# Sheet2.net
KiCad netlist of a schematic drawn in Altium Designer
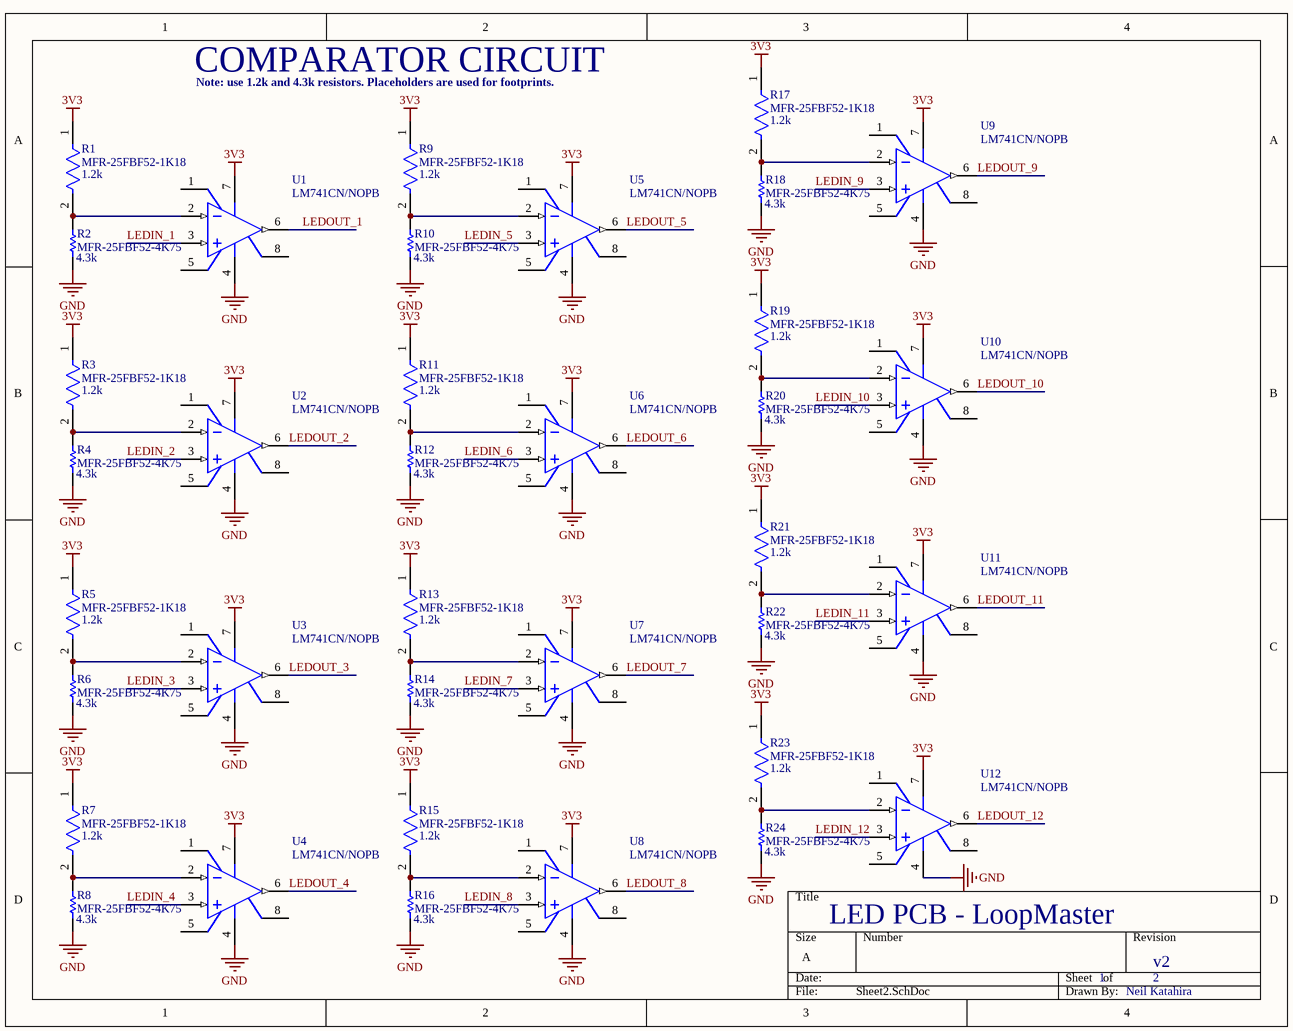
[diagram p0: Sheet2.SchDoc]

(export (version "E")
  (design (tool "Eeschema 10.0.6"))
  (components
    (comp (ref "R1")
      (value "MFR-25FBF52-1K18")
      (footprint "FP-MFR-25-MFG")
      (description "1.18 kOhms ±1% 0.25W, 1/4W Through Hole Resistor Axial  Metal Film")
      (fields (field (name "MANUFACTURER") "Yageo"))
      (libsource (lib "Altium Content Vault") (part "1029c3af85768c4190bb7ad29bc67b5"))
    )
    (comp (ref "R2")
      (value "MFR-25FBF52-4K75")
      (footprint "RESA60-630X240")
      (description "Axial Resistor, 4.75 KOhm, +/- 1%, 0.25 W, -55 to 155 degC, 2-Pin THD, RoHS, Bulk")
      (fields (field (name "TOLERANCE") "10%"))
      (libsource (lib "Altium Content Vault") (part "RES-2"))
    )
    (comp (ref "R3")
      (value "MFR-25FBF52-1K18")
      (footprint "FP-MFR-25-MFG")
      (description "1.18 kOhms ±1% 0.25W, 1/4W Through Hole Resistor Axial  Metal Film")
      (fields (field (name "MANUFACTURER") "Yageo"))
      (libsource (lib "Altium Content Vault") (part "1029c3af85768c4190bb7ad29bc67b5"))
    )
    (comp (ref "R4")
      (value "MFR-25FBF52-4K75")
      (footprint "RESA60-630X240")
      (description "Axial Resistor, 4.75 KOhm, +/- 1%, 0.25 W, -55 to 155 degC, 2-Pin THD, RoHS, Bulk")
      (fields (field (name "TOLERANCE") "10%"))
      (libsource (lib "Altium Content Vault") (part "RES-2"))
    )
    (comp (ref "R5")
      (value "MFR-25FBF52-1K18")
      (footprint "FP-MFR-25-MFG")
      (description "1.18 kOhms ±1% 0.25W, 1/4W Through Hole Resistor Axial  Metal Film")
      (fields (field (name "MANUFACTURER") "Yageo"))
      (libsource (lib "Altium Content Vault") (part "1029c3af85768c4190bb7ad29bc67b5"))
    )
    (comp (ref "R6")
      (value "MFR-25FBF52-4K75")
      (footprint "RESA60-630X240")
      (description "Axial Resistor, 4.75 KOhm, +/- 1%, 0.25 W, -55 to 155 degC, 2-Pin THD, RoHS, Bulk")
      (fields (field (name "TOLERANCE") "10%"))
      (libsource (lib "Altium Content Vault") (part "RES-2"))
    )
    (comp (ref "R7")
      (value "MFR-25FBF52-1K18")
      (footprint "FP-MFR-25-MFG")
      (description "1.18 kOhms ±1% 0.25W, 1/4W Through Hole Resistor Axial  Metal Film")
      (fields (field (name "MANUFACTURER") "Yageo"))
      (libsource (lib "Altium Content Vault") (part "1029c3af85768c4190bb7ad29bc67b5"))
    )
    (comp (ref "R8")
      (value "MFR-25FBF52-4K75")
      (footprint "RESA60-630X240")
      (description "Axial Resistor, 4.75 KOhm, +/- 1%, 0.25 W, -55 to 155 degC, 2-Pin THD, RoHS, Bulk")
      (fields (field (name "TOLERANCE") "10%"))
      (libsource (lib "Altium Content Vault") (part "RES-2"))
    )
    (comp (ref "R9")
      (value "MFR-25FBF52-1K18")
      (footprint "FP-MFR-25-MFG")
      (description "1.18 kOhms ±1% 0.25W, 1/4W Through Hole Resistor Axial  Metal Film")
      (fields (field (name "MANUFACTURER") "Yageo"))
      (libsource (lib "Altium Content Vault") (part "1029c3af85768c4190bb7ad29bc67b5"))
    )
    (comp (ref "R10")
      (value "MFR-25FBF52-4K75")
      (footprint "RESA60-630X240")
      (description "Axial Resistor, 4.75 KOhm, +/- 1%, 0.25 W, -55 to 155 degC, 2-Pin THD, RoHS, Bulk")
      (fields (field (name "TOLERANCE") "10%"))
      (libsource (lib "Altium Content Vault") (part "RES-2"))
    )
    (comp (ref "R11")
      (value "MFR-25FBF52-1K18")
      (footprint "FP-MFR-25-MFG")
      (description "1.18 kOhms ±1% 0.25W, 1/4W Through Hole Resistor Axial  Metal Film")
      (fields (field (name "MANUFACTURER") "Yageo"))
      (libsource (lib "Altium Content Vault") (part "1029c3af85768c4190bb7ad29bc67b5"))
    )
    (comp (ref "R12")
      (value "MFR-25FBF52-4K75")
      (footprint "RESA60-630X240")
      (description "Axial Resistor, 4.75 KOhm, +/- 1%, 0.25 W, -55 to 155 degC, 2-Pin THD, RoHS, Bulk")
      (fields (field (name "TOLERANCE") "10%"))
      (libsource (lib "Altium Content Vault") (part "RES-2"))
    )
    (comp (ref "R13")
      (value "MFR-25FBF52-1K18")
      (footprint "FP-MFR-25-MFG")
      (description "1.18 kOhms ±1% 0.25W, 1/4W Through Hole Resistor Axial  Metal Film")
      (fields (field (name "MANUFACTURER") "Yageo"))
      (libsource (lib "Altium Content Vault") (part "1029c3af85768c4190bb7ad29bc67b5"))
    )
    (comp (ref "R14")
      (value "MFR-25FBF52-4K75")
      (footprint "RESA60-630X240")
      (description "Axial Resistor, 4.75 KOhm, +/- 1%, 0.25 W, -55 to 155 degC, 2-Pin THD, RoHS, Bulk")
      (fields (field (name "TOLERANCE") "10%"))
      (libsource (lib "Altium Content Vault") (part "RES-2"))
    )
    (comp (ref "R15")
      (value "MFR-25FBF52-1K18")
      (footprint "FP-MFR-25-MFG")
      (description "1.18 kOhms ±1% 0.25W, 1/4W Through Hole Resistor Axial  Metal Film")
      (fields (field (name "MANUFACTURER") "Yageo"))
      (libsource (lib "Altium Content Vault") (part "1029c3af85768c4190bb7ad29bc67b5"))
    )
    (comp (ref "R16")
      (value "MFR-25FBF52-4K75")
      (footprint "RESA60-630X240")
      (description "Axial Resistor, 4.75 KOhm, +/- 1%, 0.25 W, -55 to 155 degC, 2-Pin THD, RoHS, Bulk")
      (fields (field (name "TOLERANCE") "10%"))
      (libsource (lib "Altium Content Vault") (part "RES-2"))
    )
    (comp (ref "R17")
      (value "MFR-25FBF52-1K18")
      (footprint "FP-MFR-25-MFG")
      (description "1.18 kOhms ±1% 0.25W, 1/4W Through Hole Resistor Axial  Metal Film")
      (fields (field (name "MANUFACTURER") "Yageo"))
      (libsource (lib "Altium Content Vault") (part "1029c3af85768c4190bb7ad29bc67b5"))
    )
    (comp (ref "R18")
      (value "MFR-25FBF52-4K75")
      (footprint "RESA60-630X240")
      (description "Axial Resistor, 4.75 KOhm, +/- 1%, 0.25 W, -55 to 155 degC, 2-Pin THD, RoHS, Bulk")
      (fields (field (name "TOLERANCE") "10%"))
      (libsource (lib "Altium Content Vault") (part "RES-2"))
    )
    (comp (ref "R19")
      (value "MFR-25FBF52-1K18")
      (footprint "FP-MFR-25-MFG")
      (description "1.18 kOhms ±1% 0.25W, 1/4W Through Hole Resistor Axial  Metal Film")
      (fields (field (name "MANUFACTURER") "Yageo"))
      (libsource (lib "Altium Content Vault") (part "1029c3af85768c4190bb7ad29bc67b5"))
    )
    (comp (ref "R20")
      (value "MFR-25FBF52-4K75")
      (footprint "RESA60-630X240")
      (description "Axial Resistor, 4.75 KOhm, +/- 1%, 0.25 W, -55 to 155 degC, 2-Pin THD, RoHS, Bulk")
      (fields (field (name "TOLERANCE") "10%"))
      (libsource (lib "Altium Content Vault") (part "RES-2"))
    )
    (comp (ref "R21")
      (value "MFR-25FBF52-1K18")
      (footprint "FP-MFR-25-MFG")
      (description "1.18 kOhms ±1% 0.25W, 1/4W Through Hole Resistor Axial  Metal Film")
      (fields (field (name "MANUFACTURER") "Yageo"))
      (libsource (lib "Altium Content Vault") (part "1029c3af85768c4190bb7ad29bc67b5"))
    )
    (comp (ref "R22")
      (value "MFR-25FBF52-4K75")
      (footprint "RESA60-630X240")
      (description "Axial Resistor, 4.75 KOhm, +/- 1%, 0.25 W, -55 to 155 degC, 2-Pin THD, RoHS, Bulk")
      (fields (field (name "TOLERANCE") "10%"))
      (libsource (lib "Altium Content Vault") (part "RES-2"))
    )
    (comp (ref "R23")
      (value "MFR-25FBF52-1K18")
      (footprint "FP-MFR-25-MFG")
      (description "1.18 kOhms ±1% 0.25W, 1/4W Through Hole Resistor Axial  Metal Film")
      (fields (field (name "MANUFACTURER") "Yageo"))
      (libsource (lib "Altium Content Vault") (part "1029c3af85768c4190bb7ad29bc67b5"))
    )
    (comp (ref "R24")
      (value "MFR-25FBF52-4K75")
      (footprint "RESA60-630X240")
      (description "Axial Resistor, 4.75 KOhm, +/- 1%, 0.25 W, -55 to 155 degC, 2-Pin THD, RoHS, Bulk")
      (fields (field (name "TOLERANCE") "10%"))
      (libsource (lib "Altium Content Vault") (part "RES-2"))
    )
    (comp (ref "U1")
      (value "LM741CN/NOPB")
      (footprint "P0008A")
      (description "Operational Amplifier, 8-pin MDIP, Pb-Free")
      (fields (field (name "MANUFACTURER") "Texas Instruments"))
      (libsource (lib "Altium Content Vault") (part "AMP-OPA-LM741-8"))
    )
    (comp (ref "U2")
      (value "LM741CN/NOPB")
      (footprint "P0008A")
      (description "Operational Amplifier, 8-pin MDIP, Pb-Free")
      (fields (field (name "MANUFACTURER") "Texas Instruments"))
      (libsource (lib "Altium Content Vault") (part "AMP-OPA-LM741-8"))
    )
    (comp (ref "U3")
      (value "LM741CN/NOPB")
      (footprint "P0008A")
      (description "Operational Amplifier, 8-pin MDIP, Pb-Free")
      (fields (field (name "MANUFACTURER") "Texas Instruments"))
      (libsource (lib "Altium Content Vault") (part "AMP-OPA-LM741-8"))
    )
    (comp (ref "U4")
      (value "LM741CN/NOPB")
      (footprint "P0008A")
      (description "Operational Amplifier, 8-pin MDIP, Pb-Free")
      (fields (field (name "MANUFACTURER") "Texas Instruments"))
      (libsource (lib "Altium Content Vault") (part "AMP-OPA-LM741-8"))
    )
    (comp (ref "U5")
      (value "LM741CN/NOPB")
      (footprint "P0008A")
      (description "Operational Amplifier, 8-pin MDIP, Pb-Free")
      (fields (field (name "MANUFACTURER") "Texas Instruments"))
      (libsource (lib "Altium Content Vault") (part "AMP-OPA-LM741-8"))
    )
    (comp (ref "U6")
      (value "LM741CN/NOPB")
      (footprint "P0008A")
      (description "Operational Amplifier, 8-pin MDIP, Pb-Free")
      (fields (field (name "MANUFACTURER") "Texas Instruments"))
      (libsource (lib "Altium Content Vault") (part "AMP-OPA-LM741-8"))
    )
    (comp (ref "U7")
      (value "LM741CN/NOPB")
      (footprint "P0008A")
      (description "Operational Amplifier, 8-pin MDIP, Pb-Free")
      (fields (field (name "MANUFACTURER") "Texas Instruments"))
      (libsource (lib "Altium Content Vault") (part "AMP-OPA-LM741-8"))
    )
    (comp (ref "U8")
      (value "LM741CN/NOPB")
      (footprint "P0008A")
      (description "Operational Amplifier, 8-pin MDIP, Pb-Free")
      (fields (field (name "MANUFACTURER") "Texas Instruments"))
      (libsource (lib "Altium Content Vault") (part "AMP-OPA-LM741-8"))
    )
    (comp (ref "U9")
      (value "LM741CN/NOPB")
      (footprint "P0008A")
      (description "Operational Amplifier, 8-pin MDIP, Pb-Free")
      (fields (field (name "MANUFACTURER") "Texas Instruments"))
      (libsource (lib "Altium Content Vault") (part "AMP-OPA-LM741-8"))
    )
    (comp (ref "U10")
      (value "LM741CN/NOPB")
      (footprint "P0008A")
      (description "Operational Amplifier, 8-pin MDIP, Pb-Free")
      (fields (field (name "MANUFACTURER") "Texas Instruments"))
      (libsource (lib "Altium Content Vault") (part "AMP-OPA-LM741-8"))
    )
    (comp (ref "U11")
      (value "LM741CN/NOPB")
      (footprint "P0008A")
      (description "Operational Amplifier, 8-pin MDIP, Pb-Free")
      (fields (field (name "MANUFACTURER") "Texas Instruments"))
      (libsource (lib "Altium Content Vault") (part "AMP-OPA-LM741-8"))
    )
    (comp (ref "U12")
      (value "LM741CN/NOPB")
      (footprint "P0008A")
      (description "Operational Amplifier, 8-pin MDIP, Pb-Free")
      (fields (field (name "MANUFACTURER") "Texas Instruments"))
      (libsource (lib "Altium Content Vault") (part "AMP-OPA-LM741-8"))
    )
  )
  (nets
    (net (code "1") (name "/LEDIN_1") (class "Default")
      (node (ref "U1") (pin "3") (pinfunction "IN+_3") (pintype "input"))
    )
    (net (code "2") (name "/LEDIN_2") (class "Default")
      (node (ref "U2") (pin "3") (pinfunction "IN+_3") (pintype "input"))
    )
    (net (code "3") (name "/LEDIN_3") (class "Default")
      (node (ref "U3") (pin "3") (pinfunction "IN+_3") (pintype "input"))
    )
    (net (code "4") (name "/LEDIN_4") (class "Default")
      (node (ref "U4") (pin "3") (pinfunction "IN+_3") (pintype "input"))
    )
    (net (code "5") (name "/LEDIN_5") (class "Default")
      (node (ref "U5") (pin "3") (pinfunction "IN+_3") (pintype "input"))
    )
    (net (code "6") (name "/LEDIN_6") (class "Default")
      (node (ref "U6") (pin "3") (pinfunction "IN+_3") (pintype "input"))
    )
    (net (code "7") (name "/LEDIN_7") (class "Default")
      (node (ref "U7") (pin "3") (pinfunction "IN+_3") (pintype "input"))
    )
    (net (code "8") (name "/LEDIN_8") (class "Default")
      (node (ref "U8") (pin "3") (pinfunction "IN+_3") (pintype "input"))
    )
    (net (code "9") (name "/LEDIN_9") (class "Default")
      (node (ref "U9") (pin "3") (pinfunction "IN+_3") (pintype "input"))
    )
    (net (code "10") (name "/LEDIN_10") (class "Default")
      (node (ref "U10") (pin "3") (pinfunction "IN+_3") (pintype "input"))
    )
    (net (code "11") (name "/LEDIN_11") (class "Default")
      (node (ref "U11") (pin "3") (pinfunction "IN+_3") (pintype "input"))
    )
    (net (code "12") (name "/LEDIN_12") (class "Default")
      (node (ref "U12") (pin "3") (pinfunction "IN+_3") (pintype "input"))
    )
    (net (code "13") (name "/LEDOUT_1") (class "Default")
      (node (ref "U1") (pin "6") (pinfunction "OUT_6") (pintype "output"))
    )
    (net (code "14") (name "/LEDOUT_2") (class "Default")
      (node (ref "U2") (pin "6") (pinfunction "OUT_6") (pintype "output"))
    )
    (net (code "15") (name "/LEDOUT_3") (class "Default")
      (node (ref "U3") (pin "6") (pinfunction "OUT_6") (pintype "output"))
    )
    (net (code "16") (name "/LEDOUT_4") (class "Default")
      (node (ref "U4") (pin "6") (pinfunction "OUT_6") (pintype "output"))
    )
    (net (code "17") (name "/LEDOUT_5") (class "Default")
      (node (ref "U5") (pin "6") (pinfunction "OUT_6") (pintype "output"))
    )
    (net (code "18") (name "/LEDOUT_6") (class "Default")
      (node (ref "U6") (pin "6") (pinfunction "OUT_6") (pintype "output"))
    )
    (net (code "19") (name "/LEDOUT_7") (class "Default")
      (node (ref "U7") (pin "6") (pinfunction "OUT_6") (pintype "output"))
    )
    (net (code "20") (name "/LEDOUT_8") (class "Default")
      (node (ref "U8") (pin "6") (pinfunction "OUT_6") (pintype "output"))
    )
    (net (code "21") (name "/LEDOUT_9") (class "Default")
      (node (ref "U9") (pin "6") (pinfunction "OUT_6") (pintype "output"))
    )
    (net (code "22") (name "/LEDOUT_10") (class "Default")
      (node (ref "U10") (pin "6") (pinfunction "OUT_6") (pintype "output"))
    )
    (net (code "23") (name "/LEDOUT_11") (class "Default")
      (node (ref "U11") (pin "6") (pinfunction "OUT_6") (pintype "output"))
    )
    (net (code "24") (name "/LEDOUT_12") (class "Default")
      (node (ref "U12") (pin "6") (pinfunction "OUT_6") (pintype "output"))
    )
    (net (code "25") (name "3V3") (class "Default")
      (node (ref "R1") (pin "1") (pinfunction "1_1") (pintype "passive"))
      (node (ref "R11") (pin "1") (pinfunction "1_1") (pintype "passive"))
      (node (ref "R13") (pin "1") (pinfunction "1_1") (pintype "passive"))
      (node (ref "R15") (pin "1") (pinfunction "1_1") (pintype "passive"))
      (node (ref "R17") (pin "1") (pinfunction "1_1") (pintype "passive"))
      (node (ref "R19") (pin "1") (pinfunction "1_1") (pintype "passive"))
      (node (ref "R21") (pin "1") (pinfunction "1_1") (pintype "passive"))
      (node (ref "R23") (pin "1") (pinfunction "1_1") (pintype "passive"))
      (node (ref "R3") (pin "1") (pinfunction "1_1") (pintype "passive"))
      (node (ref "R5") (pin "1") (pinfunction "1_1") (pintype "passive"))
      (node (ref "R7") (pin "1") (pinfunction "1_1") (pintype "passive"))
      (node (ref "R9") (pin "1") (pinfunction "1_1") (pintype "passive"))
      (node (ref "U1") (pin "7") (pinfunction "V+_7") (pintype "power_in"))
      (node (ref "U10") (pin "7") (pinfunction "V+_7") (pintype "power_in"))
      (node (ref "U11") (pin "7") (pinfunction "V+_7") (pintype "power_in"))
      (node (ref "U12") (pin "7") (pinfunction "V+_7") (pintype "power_in"))
      (node (ref "U2") (pin "7") (pinfunction "V+_7") (pintype "power_in"))
      (node (ref "U3") (pin "7") (pinfunction "V+_7") (pintype "power_in"))
      (node (ref "U4") (pin "7") (pinfunction "V+_7") (pintype "power_in"))
      (node (ref "U5") (pin "7") (pinfunction "V+_7") (pintype "power_in"))
      (node (ref "U6") (pin "7") (pinfunction "V+_7") (pintype "power_in"))
      (node (ref "U7") (pin "7") (pinfunction "V+_7") (pintype "power_in"))
      (node (ref "U8") (pin "7") (pinfunction "V+_7") (pintype "power_in"))
      (node (ref "U9") (pin "7") (pinfunction "V+_7") (pintype "power_in"))
    )
    (net (code "26") (name "GND") (class "Default")
      (node (ref "R10") (pin "1") (pinfunction "1_1") (pintype "passive"))
      (node (ref "R12") (pin "1") (pinfunction "1_1") (pintype "passive"))
      (node (ref "R14") (pin "1") (pinfunction "1_1") (pintype "passive"))
      (node (ref "R16") (pin "1") (pinfunction "1_1") (pintype "passive"))
      (node (ref "R18") (pin "1") (pinfunction "1_1") (pintype "passive"))
      (node (ref "R2") (pin "1") (pinfunction "1_1") (pintype "passive"))
      (node (ref "R20") (pin "1") (pinfunction "1_1") (pintype "passive"))
      (node (ref "R22") (pin "1") (pinfunction "1_1") (pintype "passive"))
      (node (ref "R24") (pin "1") (pinfunction "1_1") (pintype "passive"))
      (node (ref "R4") (pin "1") (pinfunction "1_1") (pintype "passive"))
      (node (ref "R6") (pin "1") (pinfunction "1_1") (pintype "passive"))
      (node (ref "R8") (pin "1") (pinfunction "1_1") (pintype "passive"))
      (node (ref "U1") (pin "4") (pinfunction "V-_4") (pintype "power_in"))
      (node (ref "U10") (pin "4") (pinfunction "V-_4") (pintype "power_in"))
      (node (ref "U11") (pin "4") (pinfunction "V-_4") (pintype "power_in"))
      (node (ref "U12") (pin "4") (pinfunction "V-_4") (pintype "power_in"))
      (node (ref "U2") (pin "4") (pinfunction "V-_4") (pintype "power_in"))
      (node (ref "U3") (pin "4") (pinfunction "V-_4") (pintype "power_in"))
      (node (ref "U4") (pin "4") (pinfunction "V-_4") (pintype "power_in"))
      (node (ref "U5") (pin "4") (pinfunction "V-_4") (pintype "power_in"))
      (node (ref "U6") (pin "4") (pinfunction "V-_4") (pintype "power_in"))
      (node (ref "U7") (pin "4") (pinfunction "V-_4") (pintype "power_in"))
      (node (ref "U8") (pin "4") (pinfunction "V-_4") (pintype "power_in"))
      (node (ref "U9") (pin "4") (pinfunction "V-_4") (pintype "power_in"))
    )
    (net (code "27") (name "Net-(U1-IN-)") (class "Default")
      (node (ref "R1") (pin "2") (pinfunction "2_2") (pintype "passive"))
      (node (ref "R2") (pin "2") (pinfunction "2_2") (pintype "passive"))
      (node (ref "U1") (pin "2") (pinfunction "IN-_2") (pintype "input"))
    )
    (net (code "28") (name "Net-(U2-IN-)") (class "Default")
      (node (ref "R3") (pin "2") (pinfunction "2_2") (pintype "passive"))
      (node (ref "R4") (pin "2") (pinfunction "2_2") (pintype "passive"))
      (node (ref "U2") (pin "2") (pinfunction "IN-_2") (pintype "input"))
    )
    (net (code "29") (name "Net-(U3-IN-)") (class "Default")
      (node (ref "R5") (pin "2") (pinfunction "2_2") (pintype "passive"))
      (node (ref "R6") (pin "2") (pinfunction "2_2") (pintype "passive"))
      (node (ref "U3") (pin "2") (pinfunction "IN-_2") (pintype "input"))
    )
    (net (code "30") (name "Net-(U4-IN-)") (class "Default")
      (node (ref "R7") (pin "2") (pinfunction "2_2") (pintype "passive"))
      (node (ref "R8") (pin "2") (pinfunction "2_2") (pintype "passive"))
      (node (ref "U4") (pin "2") (pinfunction "IN-_2") (pintype "input"))
    )
    (net (code "31") (name "Net-(U5-IN-)") (class "Default")
      (node (ref "R10") (pin "2") (pinfunction "2_2") (pintype "passive"))
      (node (ref "R9") (pin "2") (pinfunction "2_2") (pintype "passive"))
      (node (ref "U5") (pin "2") (pinfunction "IN-_2") (pintype "input"))
    )
    (net (code "32") (name "Net-(U6-IN-)") (class "Default")
      (node (ref "R11") (pin "2") (pinfunction "2_2") (pintype "passive"))
      (node (ref "R12") (pin "2") (pinfunction "2_2") (pintype "passive"))
      (node (ref "U6") (pin "2") (pinfunction "IN-_2") (pintype "input"))
    )
    (net (code "33") (name "Net-(U7-IN-)") (class "Default")
      (node (ref "R13") (pin "2") (pinfunction "2_2") (pintype "passive"))
      (node (ref "R14") (pin "2") (pinfunction "2_2") (pintype "passive"))
      (node (ref "U7") (pin "2") (pinfunction "IN-_2") (pintype "input"))
    )
    (net (code "34") (name "Net-(U8-IN-)") (class "Default")
      (node (ref "R15") (pin "2") (pinfunction "2_2") (pintype "passive"))
      (node (ref "R16") (pin "2") (pinfunction "2_2") (pintype "passive"))
      (node (ref "U8") (pin "2") (pinfunction "IN-_2") (pintype "input"))
    )
    (net (code "35") (name "Net-(U9-IN-)") (class "Default")
      (node (ref "R17") (pin "2") (pinfunction "2_2") (pintype "passive"))
      (node (ref "R18") (pin "2") (pinfunction "2_2") (pintype "passive"))
      (node (ref "U9") (pin "2") (pinfunction "IN-_2") (pintype "input"))
    )
    (net (code "36") (name "Net-(U10-IN-)") (class "Default")
      (node (ref "R19") (pin "2") (pinfunction "2_2") (pintype "passive"))
      (node (ref "R20") (pin "2") (pinfunction "2_2") (pintype "passive"))
      (node (ref "U10") (pin "2") (pinfunction "IN-_2") (pintype "input"))
    )
    (net (code "37") (name "Net-(U11-IN-)") (class "Default")
      (node (ref "R21") (pin "2") (pinfunction "2_2") (pintype "passive"))
      (node (ref "R22") (pin "2") (pinfunction "2_2") (pintype "passive"))
      (node (ref "U11") (pin "2") (pinfunction "IN-_2") (pintype "input"))
    )
    (net (code "38") (name "Net-(U12-IN-)") (class "Default")
      (node (ref "R23") (pin "2") (pinfunction "2_2") (pintype "passive"))
      (node (ref "R24") (pin "2") (pinfunction "2_2") (pintype "passive"))
      (node (ref "U12") (pin "2") (pinfunction "IN-_2") (pintype "input"))
    )
    (net (code "39") (name "unconnected-(U1-NC-Pad8)") (class "Default")
      (node (ref "U1") (pin "8") (pinfunction "NC_8") (pintype "passive"))
    )
    (net (code "40") (name "unconnected-(U1-OFS_NULL-Pad1)") (class "Default")
      (node (ref "U1") (pin "1") (pinfunction "OFS_NULL_1") (pintype "passive"))
    )
    (net (code "41") (name "unconnected-(U1-OFS_NULL-Pad5)") (class "Default")
      (node (ref "U1") (pin "5") (pinfunction "OFS_NULL_5") (pintype "passive"))
    )
    (net (code "42") (name "unconnected-(U2-NC-Pad8)") (class "Default")
      (node (ref "U2") (pin "8") (pinfunction "NC_8") (pintype "passive"))
    )
    (net (code "43") (name "unconnected-(U2-OFS_NULL-Pad1)") (class "Default")
      (node (ref "U2") (pin "1") (pinfunction "OFS_NULL_1") (pintype "passive"))
    )
    (net (code "44") (name "unconnected-(U2-OFS_NULL-Pad5)") (class "Default")
      (node (ref "U2") (pin "5") (pinfunction "OFS_NULL_5") (pintype "passive"))
    )
    (net (code "45") (name "unconnected-(U3-NC-Pad8)") (class "Default")
      (node (ref "U3") (pin "8") (pinfunction "NC_8") (pintype "passive"))
    )
    (net (code "46") (name "unconnected-(U3-OFS_NULL-Pad1)") (class "Default")
      (node (ref "U3") (pin "1") (pinfunction "OFS_NULL_1") (pintype "passive"))
    )
    (net (code "47") (name "unconnected-(U3-OFS_NULL-Pad5)") (class "Default")
      (node (ref "U3") (pin "5") (pinfunction "OFS_NULL_5") (pintype "passive"))
    )
    (net (code "48") (name "unconnected-(U4-NC-Pad8)") (class "Default")
      (node (ref "U4") (pin "8") (pinfunction "NC_8") (pintype "passive"))
    )
    (net (code "49") (name "unconnected-(U4-OFS_NULL-Pad1)") (class "Default")
      (node (ref "U4") (pin "1") (pinfunction "OFS_NULL_1") (pintype "passive"))
    )
    (net (code "50") (name "unconnected-(U4-OFS_NULL-Pad5)") (class "Default")
      (node (ref "U4") (pin "5") (pinfunction "OFS_NULL_5") (pintype "passive"))
    )
    (net (code "51") (name "unconnected-(U5-NC-Pad8)") (class "Default")
      (node (ref "U5") (pin "8") (pinfunction "NC_8") (pintype "passive"))
    )
    (net (code "52") (name "unconnected-(U5-OFS_NULL-Pad1)") (class "Default")
      (node (ref "U5") (pin "1") (pinfunction "OFS_NULL_1") (pintype "passive"))
    )
    (net (code "53") (name "unconnected-(U5-OFS_NULL-Pad5)") (class "Default")
      (node (ref "U5") (pin "5") (pinfunction "OFS_NULL_5") (pintype "passive"))
    )
    (net (code "54") (name "unconnected-(U6-NC-Pad8)") (class "Default")
      (node (ref "U6") (pin "8") (pinfunction "NC_8") (pintype "passive"))
    )
    (net (code "55") (name "unconnected-(U6-OFS_NULL-Pad1)") (class "Default")
      (node (ref "U6") (pin "1") (pinfunction "OFS_NULL_1") (pintype "passive"))
    )
    (net (code "56") (name "unconnected-(U6-OFS_NULL-Pad5)") (class "Default")
      (node (ref "U6") (pin "5") (pinfunction "OFS_NULL_5") (pintype "passive"))
    )
    (net (code "57") (name "unconnected-(U7-NC-Pad8)") (class "Default")
      (node (ref "U7") (pin "8") (pinfunction "NC_8") (pintype "passive"))
    )
    (net (code "58") (name "unconnected-(U7-OFS_NULL-Pad1)") (class "Default")
      (node (ref "U7") (pin "1") (pinfunction "OFS_NULL_1") (pintype "passive"))
    )
    (net (code "59") (name "unconnected-(U7-OFS_NULL-Pad5)") (class "Default")
      (node (ref "U7") (pin "5") (pinfunction "OFS_NULL_5") (pintype "passive"))
    )
    (net (code "60") (name "unconnected-(U8-NC-Pad8)") (class "Default")
      (node (ref "U8") (pin "8") (pinfunction "NC_8") (pintype "passive"))
    )
    (net (code "61") (name "unconnected-(U8-OFS_NULL-Pad1)") (class "Default")
      (node (ref "U8") (pin "1") (pinfunction "OFS_NULL_1") (pintype "passive"))
    )
    (net (code "62") (name "unconnected-(U8-OFS_NULL-Pad5)") (class "Default")
      (node (ref "U8") (pin "5") (pinfunction "OFS_NULL_5") (pintype "passive"))
    )
    (net (code "63") (name "unconnected-(U9-NC-Pad8)") (class "Default")
      (node (ref "U9") (pin "8") (pinfunction "NC_8") (pintype "passive"))
    )
    (net (code "64") (name "unconnected-(U9-OFS_NULL-Pad1)") (class "Default")
      (node (ref "U9") (pin "1") (pinfunction "OFS_NULL_1") (pintype "passive"))
    )
    (net (code "65") (name "unconnected-(U9-OFS_NULL-Pad5)") (class "Default")
      (node (ref "U9") (pin "5") (pinfunction "OFS_NULL_5") (pintype "passive"))
    )
    (net (code "66") (name "unconnected-(U10-NC-Pad8)") (class "Default")
      (node (ref "U10") (pin "8") (pinfunction "NC_8") (pintype "passive"))
    )
    (net (code "67") (name "unconnected-(U10-OFS_NULL-Pad1)") (class "Default")
      (node (ref "U10") (pin "1") (pinfunction "OFS_NULL_1") (pintype "passive"))
    )
    (net (code "68") (name "unconnected-(U10-OFS_NULL-Pad5)") (class "Default")
      (node (ref "U10") (pin "5") (pinfunction "OFS_NULL_5") (pintype "passive"))
    )
    (net (code "69") (name "unconnected-(U11-NC-Pad8)") (class "Default")
      (node (ref "U11") (pin "8") (pinfunction "NC_8") (pintype "passive"))
    )
    (net (code "70") (name "unconnected-(U11-OFS_NULL-Pad1)") (class "Default")
      (node (ref "U11") (pin "1") (pinfunction "OFS_NULL_1") (pintype "passive"))
    )
    (net (code "71") (name "unconnected-(U11-OFS_NULL-Pad5)") (class "Default")
      (node (ref "U11") (pin "5") (pinfunction "OFS_NULL_5") (pintype "passive"))
    )
    (net (code "72") (name "unconnected-(U12-NC-Pad8)") (class "Default")
      (node (ref "U12") (pin "8") (pinfunction "NC_8") (pintype "passive"))
    )
    (net (code "73") (name "unconnected-(U12-OFS_NULL-Pad1)") (class "Default")
      (node (ref "U12") (pin "1") (pinfunction "OFS_NULL_1") (pintype "passive"))
    )
    (net (code "74") (name "unconnected-(U12-OFS_NULL-Pad5)") (class "Default")
      (node (ref "U12") (pin "5") (pinfunction "OFS_NULL_5") (pintype "passive"))
    )
  )
)
